# wateralarm.net
KiCad netlist of a schematic drawn in EAGLE
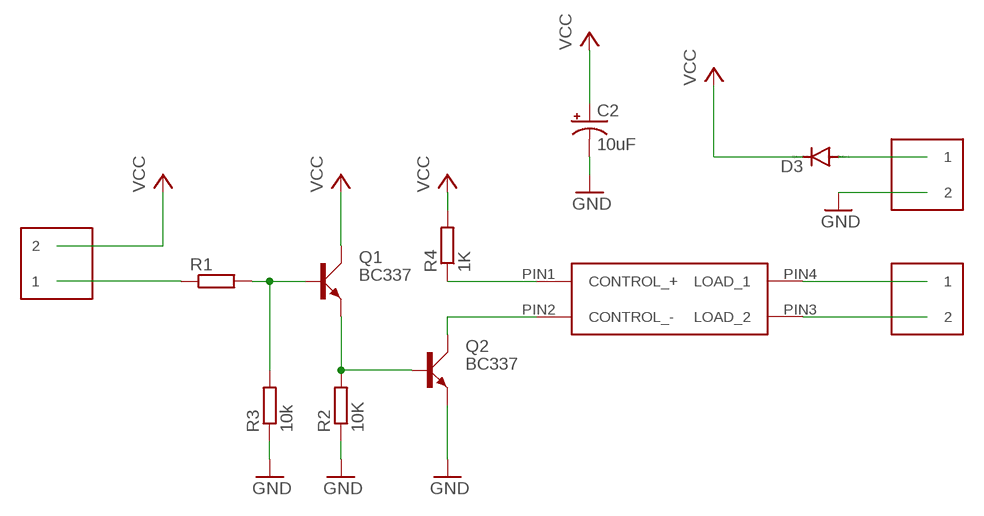
[diagram p0: schematic, sheet 1]

(export (version "E")
  (design (tool "Eeschema 10.0.6"))
  (components
    (comp (ref "C2")
      (value "10uF")
      (footprint "eagle-import:CPOL-RADIAL-2.5MM-5MM")
      (libsource (lib "eagle-import") (part "10UF-POLAR-RADIAL-2.5MM-25V-20%"))
    )
    (comp (ref "D3")
      (value "DIODE-DO214AC")
      (footprint "eagle-import:DO214AC")
      (libsource (lib "eagle-import") (part "DIODE-DO214AC"))
    )
    (comp (ref "Q1")
      (value "BC337")
      (footprint "eagle-import:SOT54A")
      (libsource (lib "eagle-import") (part "BC337"))
    )
    (comp (ref "Q2")
      (value "BC337")
      (footprint "eagle-import:SOT54A")
      (libsource (lib "eagle-import") (part "BC337"))
    )
    (comp (ref "R1")
      (value "R-EU_R0805")
      (footprint "eagle-import:R0805")
      (libsource (lib "eagle-import") (part "R-EU_R0805"))
    )
    (comp (ref "R2")
      (value "10K")
      (footprint "eagle-import:R0805")
      (libsource (lib "eagle-import") (part "R-EU_R0805"))
    )
    (comp (ref "R3")
      (value "10k")
      (footprint "eagle-import:R0805")
      (libsource (lib "eagle-import") (part "R-EU_R0805"))
    )
    (comp (ref "R4")
      (value "1K")
      (footprint "eagle-import:R0805")
      (libsource (lib "eagle-import") (part "R-EU_R0805"))
    )
    (comp (ref "U$1")
      (value "OPTO-RELAY-CPC1017N")
      (footprint "eagle-import:SOP-4")
      (libsource (lib "eagle-import") (part "OPTO-RELAY-CPC1017N"))
    )
    (comp (ref "U$2")
      (value "KF350-P2")
      (footprint "eagle-import:KF350-2P")
      (libsource (lib "eagle-import") (part "KF350-P2"))
    )
    (comp (ref "U$3")
      (value "KF350-P2")
      (footprint "eagle-import:KF350-2P")
      (libsource (lib "eagle-import") (part "KF350-P2"))
    )
    (comp (ref "U$4")
      (value "KF350-P2")
      (footprint "eagle-import:KF350-2P")
      (libsource (lib "eagle-import") (part "KF350-P2"))
    )
  )
  (nets
    (net (code "1") (name "GND") (class "Default")
      (node (ref "C2") (pin "2") (pinfunction "-_2") (pintype "passive"))
      (node (ref "Q2") (pin "E") (pinfunction "E_E") (pintype "passive"))
      (node (ref "R2") (pin "1") (pinfunction "1_1") (pintype "passive"))
      (node (ref "R3") (pin "1") (pinfunction "1_1") (pintype "passive"))
      (node (ref "U$3") (pin "2") (pinfunction "2_2") (pintype "bidirectional"))
    )
    (net (code "2") (name "Net-(D3-PadA)") (class "Default")
      (node (ref "D3") (pin "A") (pinfunction "A_A") (pintype "passive"))
      (node (ref "U$3") (pin "1") (pinfunction "1_1") (pintype "bidirectional"))
    )
    (net (code "3") (name "Net-(Q1-PadB)") (class "Default")
      (node (ref "Q1") (pin "B") (pinfunction "B_B") (pintype "passive"))
      (node (ref "R1") (pin "2") (pinfunction "2_2") (pintype "passive"))
      (node (ref "R3") (pin "2") (pinfunction "2_2") (pintype "passive"))
    )
    (net (code "4") (name "Net-(Q1-PadE)") (class "Default")
      (node (ref "Q1") (pin "E") (pinfunction "E_E") (pintype "passive"))
      (node (ref "Q2") (pin "B") (pinfunction "B_B") (pintype "passive"))
      (node (ref "R2") (pin "2") (pinfunction "2_2") (pintype "passive"))
    )
    (net (code "5") (name "Net-(R1-Pad1)") (class "Default")
      (node (ref "R1") (pin "1") (pinfunction "1_1") (pintype "passive"))
      (node (ref "U$4") (pin "1") (pinfunction "1_1") (pintype "bidirectional"))
    )
    (net (code "6") (name "Net-(U$1-CONTROL_+)") (class "Default")
      (node (ref "R4") (pin "1") (pinfunction "1_1") (pintype "passive"))
      (node (ref "U$1") (pin "PIN1") (pinfunction "CONTROL_+_PIN1") (pintype "bidirectional"))
    )
    (net (code "7") (name "Net-(U$1-CONTROL_-)") (class "Default")
      (node (ref "Q2") (pin "C") (pinfunction "C_C") (pintype "passive"))
      (node (ref "U$1") (pin "PIN2") (pinfunction "CONTROL_-_PIN2") (pintype "bidirectional"))
    )
    (net (code "8") (name "Net-(U$1-LOAD_1)") (class "Default")
      (node (ref "U$1") (pin "PIN4") (pinfunction "LOAD_1_PIN4") (pintype "bidirectional"))
      (node (ref "U$2") (pin "1") (pinfunction "1_1") (pintype "bidirectional"))
    )
    (net (code "9") (name "Net-(U$1-LOAD_2)") (class "Default")
      (node (ref "U$1") (pin "PIN3") (pinfunction "LOAD_2_PIN3") (pintype "bidirectional"))
      (node (ref "U$2") (pin "2") (pinfunction "2_2") (pintype "bidirectional"))
    )
    (net (code "10") (name "VCC") (class "Default")
      (node (ref "C2") (pin "1") (pinfunction "+_1") (pintype "passive"))
      (node (ref "D3") (pin "C") (pinfunction "C_C") (pintype "passive"))
      (node (ref "Q1") (pin "C") (pinfunction "C_C") (pintype "passive"))
      (node (ref "R4") (pin "2") (pinfunction "2_2") (pintype "passive"))
      (node (ref "U$4") (pin "2") (pinfunction "2_2") (pintype "bidirectional"))
    )
  )
)
